# picopower.net
KiCad netlist of a schematic drawn in EAGLE
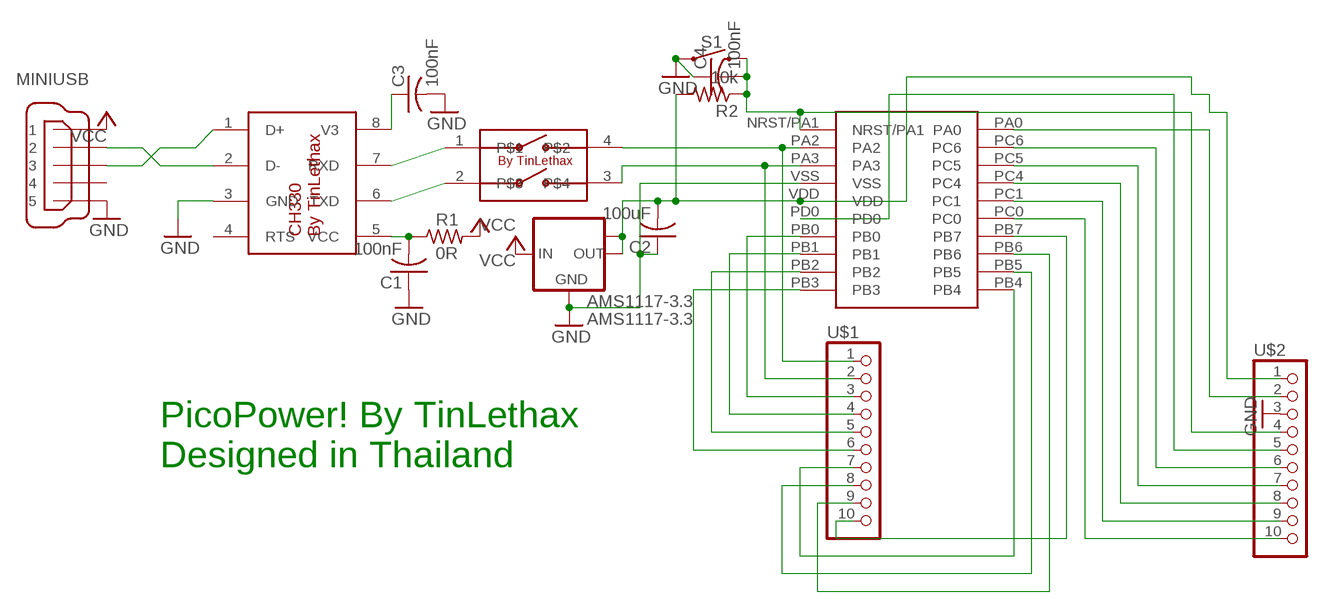
[diagram p0: schematic, sheet 1]

(export (version "E")
  (design (tool "Eeschema 10.0.6"))
  (components
    (comp (ref "2DIP")
      (value "2DIPSWITCH")
      (footprint "eagle-import:SOIC127P835X230-4N")
      (libsource (lib "eagle-import") (part "2DIPSWITCH"))
    )
    (comp (ref "AMS1117-3.3")
      (value "AMS1117-3.3")
      (footprint "eagle-import:SOT223")
      (libsource (lib "eagle-import") (part "LM1117MPX-3.3"))
    )
    (comp (ref "C1")
      (value "100nF")
      (footprint "eagle-import:C0603K")
      (libsource (lib "eagle-import") (part "C-USC0603K"))
    )
    (comp (ref "C2")
      (value "100uF")
      (footprint "eagle-import:C0603K")
      (libsource (lib "eagle-import") (part "C-USC0603K"))
    )
    (comp (ref "C3")
      (value "100nF")
      (footprint "eagle-import:C0603K")
      (libsource (lib "eagle-import") (part "C-USC0603K"))
    )
    (comp (ref "C4")
      (value "100nF")
      (footprint "eagle-import:C0603K")
      (libsource (lib "eagle-import") (part "C-USC0603K"))
    )
    (comp (ref "CH330")
      (value "CH330")
      (footprint "eagle-import:SOIC127P600X150-8N")
      (libsource (lib "eagle-import") (part "CH330"))
    )
    (comp (ref "MINIUSB")
      (value "MINI-USB-UX60A-MB-5ST")
      (footprint "eagle-import:UX60A-MB-5ST")
      (libsource (lib "eagle-import") (part "MINI-USB-UX60A-MB-5ST"))
    )
    (comp (ref "R1")
      (value "0R")
      (footprint "eagle-import:R0603")
      (libsource (lib "eagle-import") (part "R-US_R0603"))
    )
    (comp (ref "R2")
      (value "10k")
      (footprint "eagle-import:R0603")
      (libsource (lib "eagle-import") (part "R-US_R0603"))
    )
    (comp (ref "S1")
      (value "MOMENTARY-SWITCH-SPST-SMD-6.0X3.5MM")
      (footprint "eagle-import:TACTILE_SWITCH_SMD_6.0X3.5MM")
      (libsource (lib "eagle-import") (part "MOMENTARY-SWITCH-SPST-SMD-6.0X3.5MM"))
    )
    (comp (ref "STM8L")
      (value "STM8L151F3")
      (footprint "eagle-import:UFQFPN-20")
      (libsource (lib "eagle-import") (part "STM8L151F3"))
    )
    (comp (ref "U$1")
      (value "PINHD-1X10")
      (footprint "eagle-import:1X10-BIG")
      (libsource (lib "eagle-import") (part "PINHD-1X10"))
    )
    (comp (ref "U$2")
      (value "PINHD-1X10")
      (footprint "eagle-import:1X10-BIG")
      (libsource (lib "eagle-import") (part "PINHD-1X10"))
    )
  )
  (nets
    (net (code "1") (name "GND") (class "Default")
      (node (ref "AMS1117-3.3") (pin "1") (pinfunction "GND_1") (pintype "input"))
      (node (ref "C1") (pin "1") (pinfunction "1_1") (pintype "passive"))
      (node (ref "C2") (pin "1") (pinfunction "1_1") (pintype "passive"))
      (node (ref "C3") (pin "2") (pinfunction "2_2") (pintype "passive"))
      (node (ref "C4") (pin "1") (pinfunction "1_1") (pintype "passive"))
      (node (ref "CH330") (pin "3") (pinfunction "GND_3") (pintype "bidirectional"))
      (node (ref "MINIUSB") (pin "5") (pinfunction "5_5") (pintype "input"))
      (node (ref "S1") (pin "1") (pinfunction "1_1") (pintype "passive"))
      (node (ref "STM8L") (pin "VSS") (pinfunction "VSS_VSS") (pintype "bidirectional"))
      (node (ref "U$2") (pin "3") (pinfunction "3_3") (pintype "passive"))
    )
    (net (code "2") (name "Net-(2DIP-P$1)") (class "Default")
      (node (ref "2DIP") (pin "1") (pinfunction "P$1_1") (pintype "bidirectional"))
      (node (ref "CH330") (pin "7") (pinfunction "RXD_7") (pintype "bidirectional"))
    )
    (net (code "3") (name "Net-(2DIP-P$2)") (class "Default")
      (node (ref "2DIP") (pin "4") (pinfunction "P$2_4") (pintype "bidirectional"))
      (node (ref "STM8L") (pin "PA2") (pinfunction "PA2_PA2") (pintype "bidirectional"))
      (node (ref "U$1") (pin "1") (pinfunction "1_1") (pintype "passive"))
    )
    (net (code "4") (name "Net-(2DIP-P$3)") (class "Default")
      (node (ref "2DIP") (pin "2") (pinfunction "P$3_2") (pintype "bidirectional"))
      (node (ref "CH330") (pin "6") (pinfunction "TXD_6") (pintype "bidirectional"))
    )
    (net (code "5") (name "Net-(2DIP-P$4)") (class "Default")
      (node (ref "2DIP") (pin "3") (pinfunction "P$4_3") (pintype "bidirectional"))
      (node (ref "STM8L") (pin "PA3") (pinfunction "PA3_PA3") (pintype "bidirectional"))
      (node (ref "U$1") (pin "2") (pinfunction "2_2") (pintype "passive"))
    )
    (net (code "6") (name "Net-(AMS1117-3.3-OUT)") (class "Default")
      (node (ref "AMS1117-3.3") (pin "2") (pinfunction "OUT_2") (pintype "passive"))
      (node (ref "AMS1117-3.3") (pin "TAB") (pinfunction "OUT1_TAB") (pintype "passive"))
      (node (ref "C2") (pin "2") (pinfunction "2_2") (pintype "passive"))
      (node (ref "R2") (pin "2") (pinfunction "2_2") (pintype "passive"))
      (node (ref "STM8L") (pin "VDD") (pinfunction "VDD_VDD") (pintype "bidirectional"))
      (node (ref "U$2") (pin "1") (pinfunction "1_1") (pintype "passive"))
    )
    (net (code "7") (name "Net-(C4-Pad2)") (class "Default")
      (node (ref "C4") (pin "2") (pinfunction "2_2") (pintype "passive"))
      (node (ref "R2") (pin "1") (pinfunction "1_1") (pintype "passive"))
      (node (ref "S1") (pin "2") (pinfunction "2_2") (pintype "passive"))
      (node (ref "STM8L") (pin "NRST/PA1") (pinfunction "NRST/PA1_NRST/PA1") (pintype "bidirectional"))
      (node (ref "U$2") (pin "4") (pinfunction "4_4") (pintype "passive"))
    )
    (net (code "8") (name "Net-(CH330-D+)") (class "Default")
      (node (ref "CH330") (pin "1") (pinfunction "D+_1") (pintype "bidirectional"))
      (node (ref "MINIUSB") (pin "3") (pinfunction "3_3") (pintype "input"))
    )
    (net (code "9") (name "Net-(CH330-D-)") (class "Default")
      (node (ref "CH330") (pin "2") (pinfunction "D-_2") (pintype "bidirectional"))
      (node (ref "MINIUSB") (pin "2") (pinfunction "2_2") (pintype "input"))
    )
    (net (code "10") (name "Net-(CH330-V3)") (class "Default")
      (node (ref "C3") (pin "1") (pinfunction "1_1") (pintype "passive"))
      (node (ref "CH330") (pin "8") (pinfunction "V3_8") (pintype "bidirectional"))
    )
    (net (code "11") (name "Net-(CH330-VCC)") (class "Default")
      (node (ref "C1") (pin "2") (pinfunction "2_2") (pintype "passive"))
      (node (ref "CH330") (pin "5") (pinfunction "VCC_5") (pintype "bidirectional"))
      (node (ref "R1") (pin "1") (pinfunction "1_1") (pintype "passive"))
    )
    (net (code "12") (name "Net-(STM8L-PadPA0)") (class "Default")
      (node (ref "STM8L") (pin "PA0") (pinfunction "PA0_PA0") (pintype "bidirectional"))
      (node (ref "U$2") (pin "2") (pinfunction "2_2") (pintype "passive"))
    )
    (net (code "13") (name "Net-(STM8L-PadPB0)") (class "Default")
      (node (ref "STM8L") (pin "PB0") (pinfunction "PB0_PB0") (pintype "bidirectional"))
      (node (ref "U$1") (pin "3") (pinfunction "3_3") (pintype "passive"))
    )
    (net (code "14") (name "Net-(STM8L-PadPB1)") (class "Default")
      (node (ref "STM8L") (pin "PB1") (pinfunction "PB1_PB1") (pintype "bidirectional"))
      (node (ref "U$1") (pin "4") (pinfunction "4_4") (pintype "passive"))
    )
    (net (code "15") (name "Net-(STM8L-PadPB2)") (class "Default")
      (node (ref "STM8L") (pin "PB2") (pinfunction "PB2_PB2") (pintype "bidirectional"))
      (node (ref "U$1") (pin "5") (pinfunction "5_5") (pintype "passive"))
    )
    (net (code "16") (name "Net-(STM8L-PadPB3)") (class "Default")
      (node (ref "STM8L") (pin "PB3") (pinfunction "PB3_PB3") (pintype "bidirectional"))
      (node (ref "U$1") (pin "6") (pinfunction "6_6") (pintype "passive"))
    )
    (net (code "17") (name "Net-(STM8L-PadPB4)") (class "Default")
      (node (ref "STM8L") (pin "PB4") (pinfunction "PB4_PB4") (pintype "bidirectional"))
      (node (ref "U$1") (pin "7") (pinfunction "7_7") (pintype "passive"))
    )
    (net (code "18") (name "Net-(STM8L-PadPB5)") (class "Default")
      (node (ref "STM8L") (pin "PB5") (pinfunction "PB5_PB5") (pintype "bidirectional"))
      (node (ref "U$1") (pin "8") (pinfunction "8_8") (pintype "passive"))
    )
    (net (code "19") (name "Net-(STM8L-PadPB6)") (class "Default")
      (node (ref "STM8L") (pin "PB6") (pinfunction "PB6_PB6") (pintype "bidirectional"))
      (node (ref "U$1") (pin "9") (pinfunction "9_9") (pintype "passive"))
    )
    (net (code "20") (name "Net-(STM8L-PadPB7)") (class "Default")
      (node (ref "STM8L") (pin "PB7") (pinfunction "PB7_PB7") (pintype "bidirectional"))
      (node (ref "U$1") (pin "10") (pinfunction "10_10") (pintype "passive"))
    )
    (net (code "21") (name "Net-(STM8L-PadPC0)") (class "Default")
      (node (ref "STM8L") (pin "PC0") (pinfunction "PC0_PC0") (pintype "bidirectional"))
      (node (ref "U$2") (pin "10") (pinfunction "10_10") (pintype "passive"))
    )
    (net (code "22") (name "Net-(STM8L-PadPC1)") (class "Default")
      (node (ref "STM8L") (pin "PC1") (pinfunction "PC1_PC1") (pintype "bidirectional"))
      (node (ref "U$2") (pin "9") (pinfunction "9_9") (pintype "passive"))
    )
    (net (code "23") (name "Net-(STM8L-PadPC4)") (class "Default")
      (node (ref "STM8L") (pin "PC4") (pinfunction "PC4_PC4") (pintype "bidirectional"))
      (node (ref "U$2") (pin "8") (pinfunction "8_8") (pintype "passive"))
    )
    (net (code "24") (name "Net-(STM8L-PadPC5)") (class "Default")
      (node (ref "STM8L") (pin "PC5") (pinfunction "PC5_PC5") (pintype "bidirectional"))
      (node (ref "U$2") (pin "7") (pinfunction "7_7") (pintype "passive"))
    )
    (net (code "25") (name "Net-(STM8L-PadPC6)") (class "Default")
      (node (ref "STM8L") (pin "PC6") (pinfunction "PC6_PC6") (pintype "bidirectional"))
      (node (ref "U$2") (pin "6") (pinfunction "6_6") (pintype "passive"))
    )
    (net (code "26") (name "Net-(STM8L-PadPD0)") (class "Default")
      (node (ref "STM8L") (pin "PD0") (pinfunction "PD0_PD0") (pintype "bidirectional"))
      (node (ref "U$2") (pin "5") (pinfunction "5_5") (pintype "passive"))
    )
    (net (code "27") (name "VCC") (class "Default")
      (node (ref "AMS1117-3.3") (pin "3") (pinfunction "IN_3") (pintype "input"))
      (node (ref "MINIUSB") (pin "1") (pinfunction "1_1") (pintype "input"))
      (node (ref "R1") (pin "2") (pinfunction "2_2") (pintype "passive"))
    )
    (net (code "28") (name "unconnected-(CH330-RTS-Pad4)") (class "Default")
      (node (ref "CH330") (pin "4") (pinfunction "RTS_4") (pintype "bidirectional"))
    )
    (net (code "29") (name "unconnected-(MINIUSB-Pad4)") (class "Default")
      (node (ref "MINIUSB") (pin "4") (pinfunction "4_4") (pintype "input"))
    )
  )
)
